# chest_03_12_2018.net
KiCad netlist of a schematic drawn in EAGLE
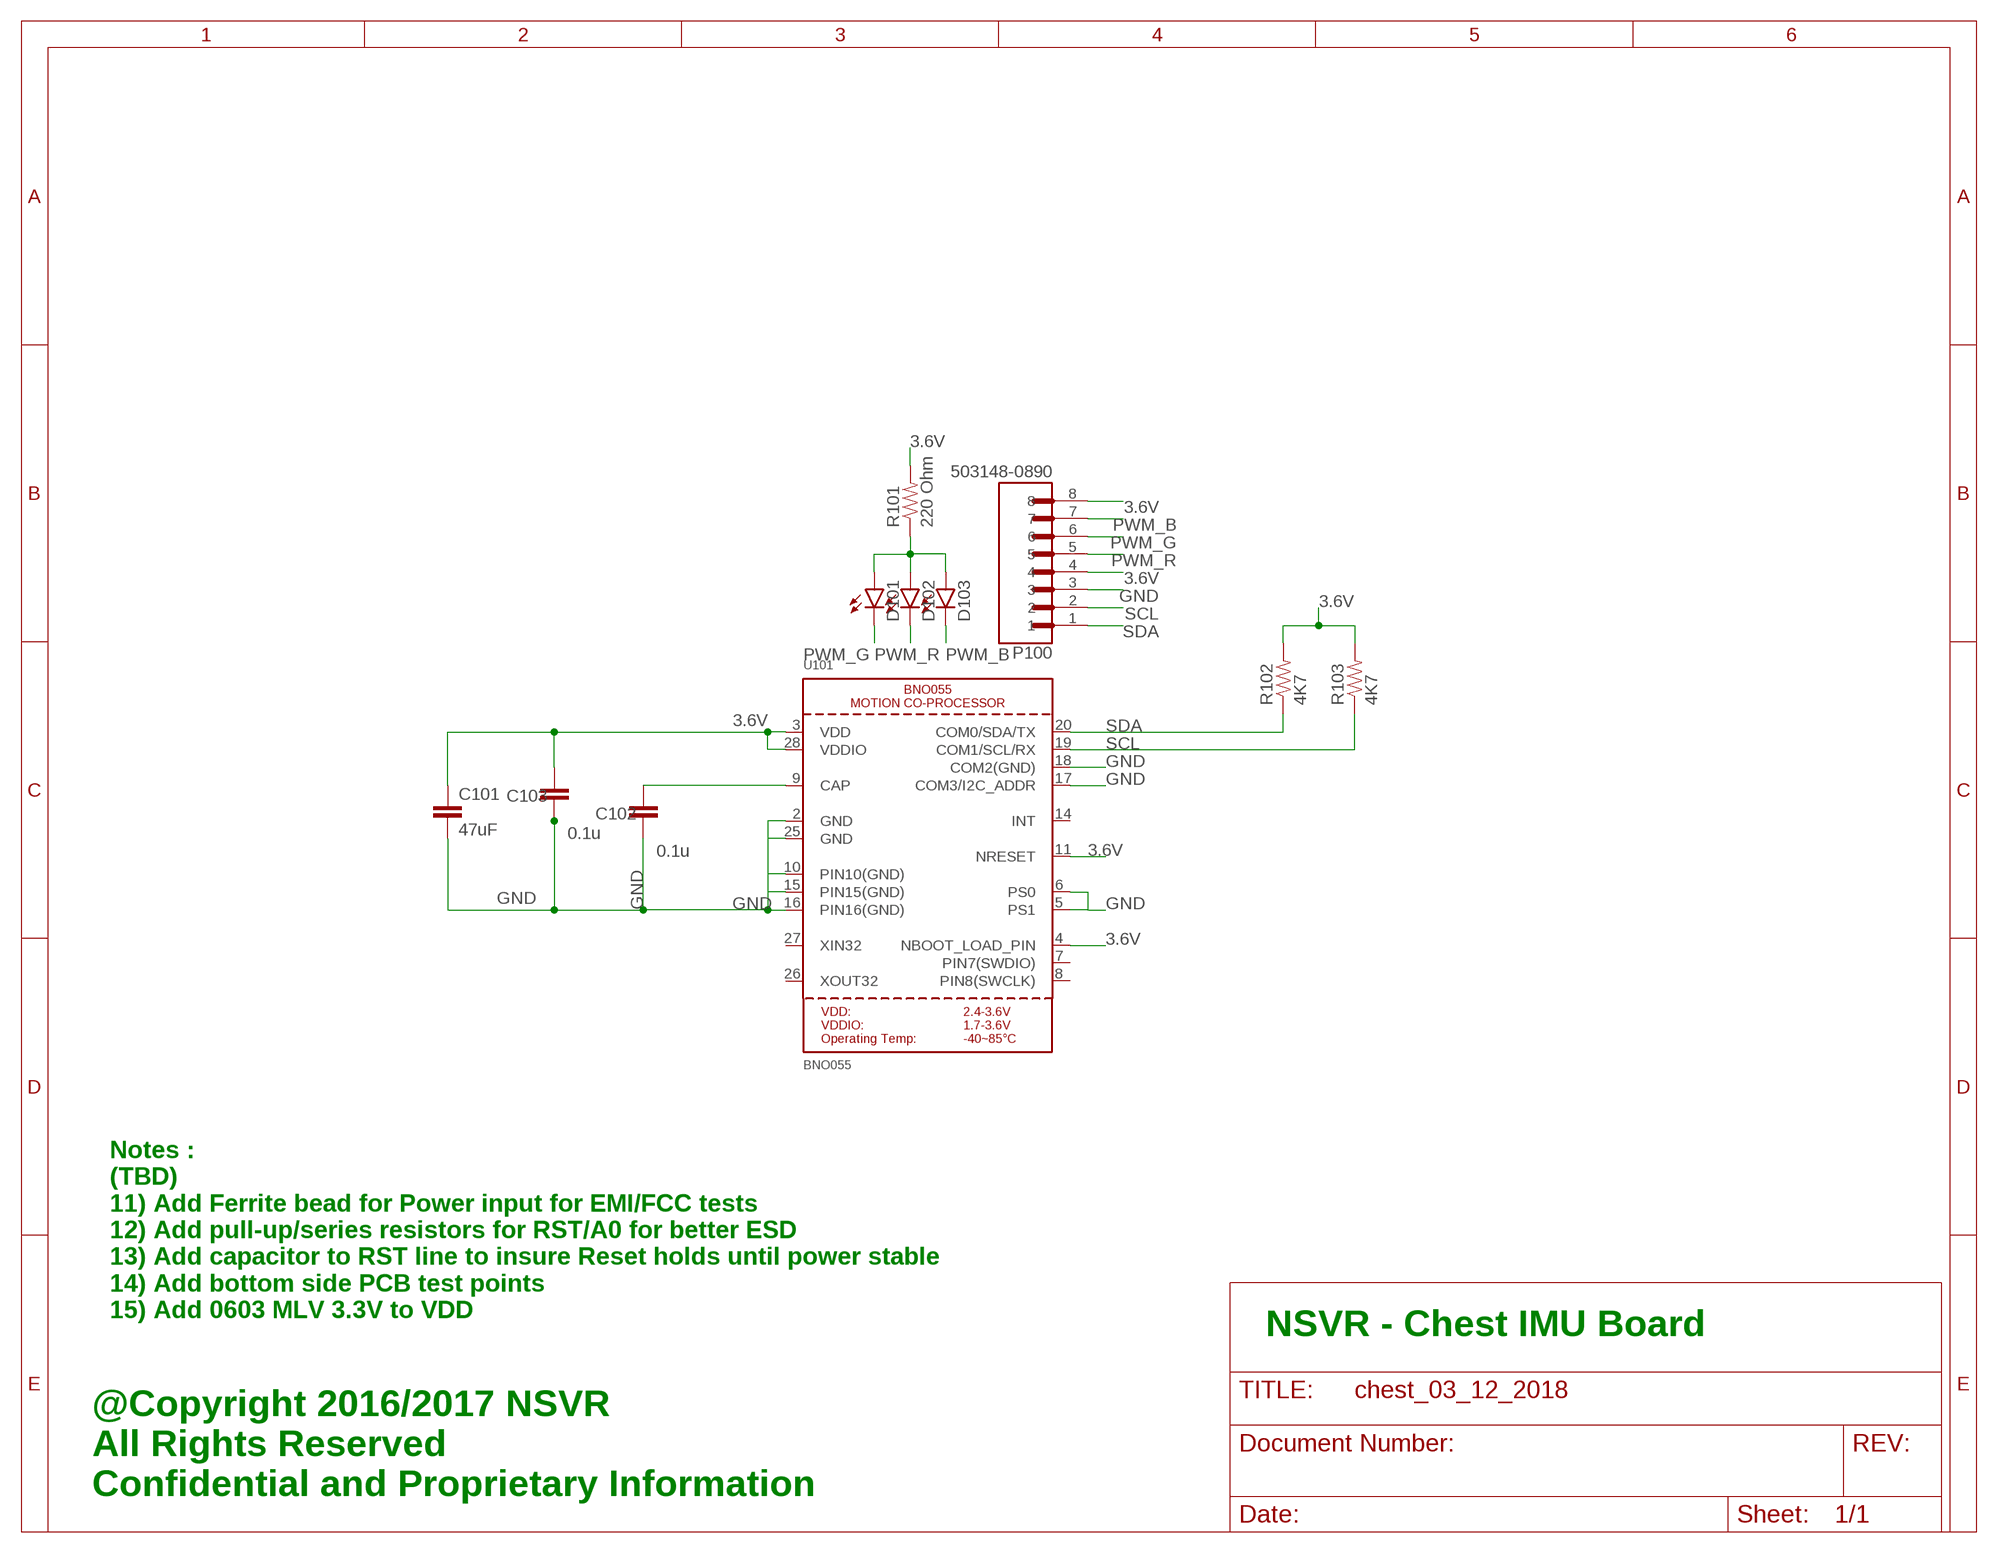
[diagram p0: schematic, sheet 1]

(export (version "E")
  (design (tool "Eeschema 10.0.6"))
  (components
    (comp (ref "C101")
      (value "47uF")
      (footprint "eagle-import:1206")
      (libsource (lib "eagle-import") (part "CAP1206"))
    )
    (comp (ref "C102")
      (value "0.1u")
      (footprint "eagle-import:0402-CAP")
      (libsource (lib "eagle-import") (part "CAP0402-CAP"))
    )
    (comp (ref "C103")
      (value "0.1u")
      (footprint "eagle-import:0402-CAP")
      (libsource (lib "eagle-import") (part "CAP0402-CAP"))
    )
    (comp (ref "D101")
      (value "LED0603")
      (footprint "eagle-import:LED-0603")
      (libsource (lib "eagle-import") (part "LED0603"))
    )
    (comp (ref "D102")
      (value "LED0603")
      (footprint "eagle-import:LED-0603")
      (libsource (lib "eagle-import") (part "LED0603"))
    )
    (comp (ref "D103")
      (value "LED0603")
      (footprint "eagle-import:LED-0603")
      (libsource (lib "eagle-import") (part "LED0603"))
    )
    (comp (ref "P100")
      (value "503148-0890")
      (footprint "eagle-import:MOLEX_503148-0890")
      (fields (field (name "MF") "Molex"))
      (libsource (lib "eagle-import") (part "503148-0890"))
    )
    (comp (ref "R101")
      (value "220 Ohm")
      (footprint "eagle-import:EIA-0402")
      (libsource (lib "eagle-import") (part "RESISTOR0402-TYP"))
    )
    (comp (ref "R102")
      (value "4K7")
      (footprint "eagle-import:EIA-0402")
      (libsource (lib "eagle-import") (part "RESISTOR0402-TYP"))
    )
    (comp (ref "R103")
      (value "4K7")
      (footprint "eagle-import:EIA-0402")
      (libsource (lib "eagle-import") (part "RESISTOR0402-TYP"))
    )
    (comp (ref "U101")
      (value "BNO055")
      (footprint "eagle-import:BNO055")
      (libsource (lib "eagle-import") (part "BNO055"))
    )
  )
  (nets
    (net (code "1") (name "/3.6V") (class "Default")
      (node (ref "C101") (pin "1") (pinfunction "1_1") (pintype "passive"))
      (node (ref "C103") (pin "1") (pinfunction "1_1") (pintype "passive"))
      (node (ref "P100") (pin "4") (pinfunction "4_4") (pintype "passive"))
      (node (ref "P100") (pin "8") (pinfunction "8_8") (pintype "passive"))
      (node (ref "R101") (pin "2") (pinfunction "2_2") (pintype "passive"))
      (node (ref "R102") (pin "2") (pinfunction "2_2") (pintype "passive"))
      (node (ref "R103") (pin "2") (pinfunction "2_2") (pintype "passive"))
      (node (ref "U101") (pin "11") (pinfunction "NRESET_11") (pintype "bidirectional"))
      (node (ref "U101") (pin "28") (pinfunction "VDDIO_28") (pintype "power_in"))
      (node (ref "U101") (pin "3") (pinfunction "VDD_3") (pintype "power_in"))
      (node (ref "U101") (pin "4") (pinfunction "NBOOT_LOAD_PIN_4") (pintype "bidirectional"))
    )
    (net (code "2") (name "/GND") (class "Default")
      (node (ref "C101") (pin "2") (pinfunction "2_2") (pintype "passive"))
      (node (ref "C102") (pin "2") (pinfunction "2_2") (pintype "passive"))
      (node (ref "C103") (pin "2") (pinfunction "2_2") (pintype "passive"))
      (node (ref "P100") (pin "3") (pinfunction "3_3") (pintype "passive"))
      (node (ref "U101") (pin "10") (pinfunction "PIN10(GND)_10") (pintype "bidirectional"))
      (node (ref "U101") (pin "15") (pinfunction "PIN15(GND)_15") (pintype "bidirectional"))
      (node (ref "U101") (pin "16") (pinfunction "PIN16(GND)_16") (pintype "bidirectional"))
      (node (ref "U101") (pin "17") (pinfunction "COM3/I2C_ADDR_17") (pintype "bidirectional"))
      (node (ref "U101") (pin "18") (pinfunction "COM2(GND)_18") (pintype "bidirectional"))
      (node (ref "U101") (pin "2") (pinfunction "GND_2") (pintype "power_in"))
      (node (ref "U101") (pin "25") (pinfunction "GND_25") (pintype "power_in"))
      (node (ref "U101") (pin "5") (pinfunction "PS1_5") (pintype "input"))
      (node (ref "U101") (pin "6") (pinfunction "PS0_6") (pintype "input"))
    )
    (net (code "3") (name "/PWM_B") (class "Default")
      (node (ref "D103") (pin "C") (pinfunction "C_C") (pintype "passive"))
      (node (ref "P100") (pin "7") (pinfunction "7_7") (pintype "passive"))
    )
    (net (code "4") (name "/PWM_G") (class "Default")
      (node (ref "D101") (pin "C") (pinfunction "C_C") (pintype "passive"))
      (node (ref "P100") (pin "6") (pinfunction "6_6") (pintype "passive"))
    )
    (net (code "5") (name "/PWM_R") (class "Default")
      (node (ref "D102") (pin "C") (pinfunction "C_C") (pintype "passive"))
      (node (ref "P100") (pin "5") (pinfunction "5_5") (pintype "passive"))
    )
    (net (code "6") (name "/SCL") (class "Default")
      (node (ref "P100") (pin "2") (pinfunction "2_2") (pintype "passive"))
      (node (ref "R103") (pin "1") (pinfunction "1_1") (pintype "passive"))
      (node (ref "U101") (pin "19") (pinfunction "COM1/SCL/RX_19") (pintype "bidirectional"))
    )
    (net (code "7") (name "/SDA") (class "Default")
      (node (ref "P100") (pin "1") (pinfunction "1_1") (pintype "passive"))
      (node (ref "R102") (pin "1") (pinfunction "1_1") (pintype "passive"))
      (node (ref "U101") (pin "20") (pinfunction "COM0/SDA/TX_20") (pintype "bidirectional"))
    )
    (net (code "8") (name "Net-(D101-PadA)") (class "Default")
      (node (ref "D101") (pin "A") (pinfunction "A_A") (pintype "passive"))
      (node (ref "D102") (pin "A") (pinfunction "A_A") (pintype "passive"))
      (node (ref "D103") (pin "A") (pinfunction "A_A") (pintype "passive"))
      (node (ref "R101") (pin "1") (pinfunction "1_1") (pintype "passive"))
    )
    (net (code "9") (name "Net-(U101-CAP)") (class "Default")
      (node (ref "C102") (pin "1") (pinfunction "1_1") (pintype "passive"))
      (node (ref "U101") (pin "9") (pinfunction "CAP_9") (pintype "passive"))
    )
    (net (code "10") (name "unconnected-(U101-INT-Pad14)") (class "Default")
      (node (ref "U101") (pin "14") (pinfunction "INT_14") (pintype "output"))
    )
    (net (code "11") (name "unconnected-(U101-PIN7(SWDIO)-Pad7)") (class "Default")
      (node (ref "U101") (pin "7") (pinfunction "PIN7(SWDIO)_7") (pintype "bidirectional"))
    )
    (net (code "12") (name "unconnected-(U101-PIN8(SWCLK)-Pad8)") (class "Default")
      (node (ref "U101") (pin "8") (pinfunction "PIN8(SWCLK)_8") (pintype "bidirectional"))
    )
    (net (code "13") (name "unconnected-(U101-XIN32-Pad27)") (class "Default")
      (node (ref "U101") (pin "27") (pinfunction "XIN32_27") (pintype "input"))
    )
    (net (code "14") (name "unconnected-(U101-XOUT32-Pad26)") (class "Default")
      (node (ref "U101") (pin "26") (pinfunction "XOUT32_26") (pintype "output"))
    )
  )
)
